# PPU2_And_Connector.net
KiCad netlist of a schematic drawn in Altium Designer
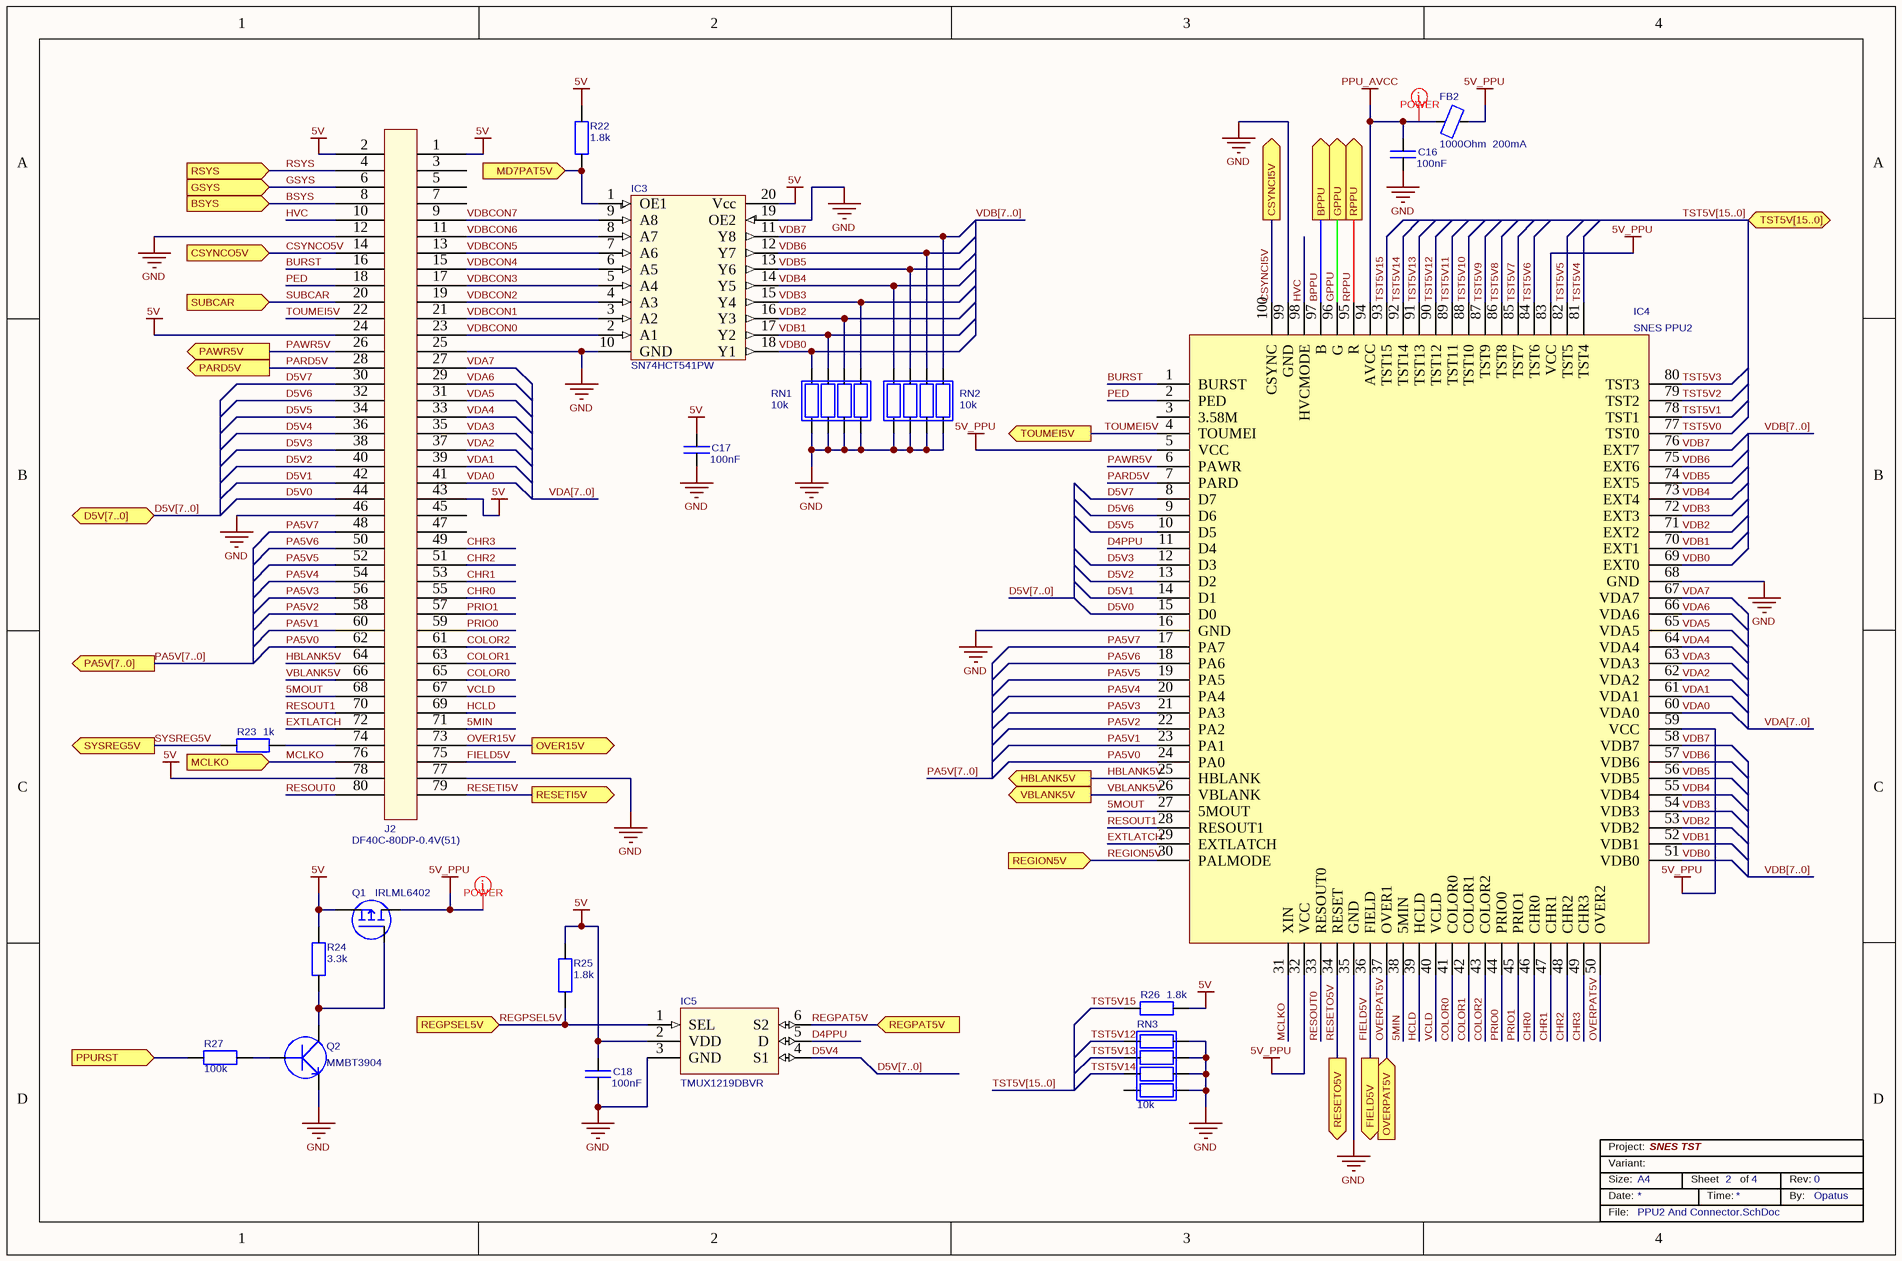
[diagram p0: PPU2 And Connector.SchDoc]

(export (version "E")
  (design (tool "Eeschema 10.0.6"))
  (components
    (comp (ref "C16")
      (value "100nF")
      (footprint "Cap_0402_Chip")
      (fields
        (field (name "TOLERANCE") "±20%")
        (field (name "Comment") "Ceramic Capacitor 100nF 10V ±20% X7R 0402")
      )
      (libsource (lib "PCB") (part "Capacitor"))
    )
    (comp (ref "C17")
      (value "100nF")
      (footprint "Cap_0402_Chip")
      (fields
        (field (name "TOLERANCE") "±20%")
        (field (name "Comment") "Ceramic Capacitor 100nF 10V ±20% X7R 0402")
      )
      (libsource (lib "PCB") (part "Capacitor"))
    )
    (comp (ref "C18")
      (value "100nF")
      (footprint "Cap_0402_Chip")
      (fields
        (field (name "TOLERANCE") "±20%")
        (field (name "Comment") "Ceramic Capacitor 100nF 10V ±20% X7R 0402")
      )
      (libsource (lib "PCB") (part "Capacitor"))
    )
    (comp (ref "FB2")
      (value "1000Ohm  200mA")
      (footprint "Ind_0402_Chip")
      (fields (field (name "MANUFACTURER_PART_NUMBER") "MMZ1005S102CT000"))
      (libsource (lib "PCB") (part "Ferrite Bead"))
    )
    (comp (ref "IC3")
      (value "SN74HCT541")
      (footprint "TSSOP20 Narrow")
      (fields (field (name "MANUFACTURER_PART_NUMBER") "SN74HCT541PW"))
      (libsource (lib "PCB") (part "SN74HCT541"))
    )
    (comp (ref "IC4")
      (value "SNES PPU2")
      (footprint "PPU100Pin")
      (description "PPU2")
      (libsource (lib "PCB") (part "PPU2100Pin"))
    )
    (comp (ref "IC5")
      (value "TMUX1219")
      (footprint "SOT23-6")
      (description "2:1 MUX")
      (fields (field (name "MANUFACTURER_PART_NUMBER") "TMUX1219DBVR"))
      (libsource (lib "PCB") (part "TMUX1219"))
    )
    (comp (ref "J2")
      (value "DF40C-80DP")
      (footprint "DF40C-80DP")
      (description "80Pole Connector")
      (fields (field (name "MANUFACTURER_PART_NUMBER") "DF40C-80DP-0.4V(51)"))
      (libsource (lib "PCB") (part "Conn 80P"))
    )
    (comp (ref "Q1") (value "IRLML6402") (footprint "SOT23_FET") (libsource (lib "PCB") (part "Mosfet1")))
    (comp (ref "Q2") (value "MMBT3904") (footprint "SOT23_Transistor") (libsource (lib "PCB") (part "T_NPN")))
    (comp (ref "R22")
      (value "1.8k")
      (footprint "Res_0402_Chip")
      (fields (field (name "TOLERANCE") "±1%") (field (name "Comment") "Resistor 1.8k 0402 ±1%"))
      (libsource (lib "PCB") (part "R"))
    )
    (comp (ref "R23")
      (value "1k")
      (footprint "Res_0402_Chip")
      (fields (field (name "TOLERANCE") "±1%") (field (name "Comment") "Resistor 1k 0402 ±1%"))
      (libsource (lib "") (part "R_1"))
    )
    (comp (ref "R24")
      (value "3.3k")
      (footprint "Res_0402_Chip")
      (fields (field (name "TOLERANCE") "±1%") (field (name "Comment") "Resistor 3.3k 0402 ±1%"))
      (libsource (lib "PCB") (part "R"))
    )
    (comp (ref "R25")
      (value "1.8k")
      (footprint "Res_0402_Chip")
      (fields (field (name "TOLERANCE") "±1%") (field (name "Comment") "Resistor 1.8k 0402 ±1%"))
      (libsource (lib "PCB") (part "R"))
    )
    (comp (ref "R26")
      (value "1.8k")
      (footprint "Res_0402_Chip")
      (fields (field (name "TOLERANCE") "±1%") (field (name "Comment") "Resistor 1.8k 0402 ±1%"))
      (libsource (lib "") (part "R_2"))
    )
    (comp (ref "R27")
      (value "100k")
      (footprint "Res_0402_Chip")
      (fields (field (name "TOLERANCE") "±1%") (field (name "Comment") "Resistor 100k 0402 ±1%"))
      (libsource (lib "") (part "R_1"))
    )
    (comp (ref "RN1")
      (value "10k")
      (footprint "1206_Array_Chip")
      (fields (field (name "TOLERANCE") "±1%") (field (name "Comment") "Resistor Network 10k 1206 ±1%"))
      (libsource (lib "PCB") (part "RNetwork"))
    )
    (comp (ref "RN2")
      (value "10k")
      (footprint "1206_Array_Chip")
      (fields (field (name "TOLERANCE") "±1%") (field (name "Comment") "Resistor Network 10k 1206 ±1%"))
      (libsource (lib "PCB") (part "RNetwork"))
    )
    (comp (ref "RN3")
      (value "10k")
      (footprint "1206_Array_Chip")
      (fields (field (name "TOLERANCE") "±1%") (field (name "Comment") "Resistor Network 10k 1206 ±1%"))
      (libsource (lib "") (part "RNetwork_1"))
    )
  )
  (nets
    (net (code "1") (name "/5MIN") (class "Default")
      (node (ref "IC4") (pin "38") (pinfunction "5MIN_38") (pintype "passive"))
      (node (ref "J2") (pin "71") (pintype "passive"))
    )
    (net (code "2") (name "/5MOUT") (class "Default")
      (node (ref "IC4") (pin "27") (pinfunction "5MOUT_27") (pintype "passive"))
      (node (ref "J2") (pin "68") (pintype "passive"))
    )
    (net (code "3") (name "/BPPU") (class "Default")
      (node (ref "IC4") (pin "97") (pinfunction "B_97") (pintype "passive"))
    )
    (net (code "4") (name "/BSYS") (class "Default") (node (ref "J2") (pin "8") (pintype "passive")))
    (net (code "5") (name "/BURST") (class "Default")
      (node (ref "IC4") (pin "1") (pinfunction "BURST_1") (pintype "passive"))
      (node (ref "J2") (pin "16") (pintype "passive"))
    )
    (net (code "6") (name "/CHR0") (class "Default")
      (node (ref "IC4") (pin "46") (pinfunction "CHR0_46") (pintype "passive"))
      (node (ref "J2") (pin "55") (pintype "passive"))
    )
    (net (code "7") (name "/CHR1") (class "Default")
      (node (ref "IC4") (pin "47") (pinfunction "CHR1_47") (pintype "passive"))
      (node (ref "J2") (pin "53") (pintype "passive"))
    )
    (net (code "8") (name "/CHR2") (class "Default")
      (node (ref "IC4") (pin "48") (pinfunction "CHR2_48") (pintype "passive"))
      (node (ref "J2") (pin "51") (pintype "passive"))
    )
    (net (code "9") (name "/CHR3") (class "Default")
      (node (ref "IC4") (pin "49") (pinfunction "CHR3_49") (pintype "passive"))
      (node (ref "J2") (pin "49") (pintype "passive"))
    )
    (net (code "10") (name "/COLOR0") (class "Default")
      (node (ref "IC4") (pin "41") (pinfunction "COLOR0_41") (pintype "passive"))
      (node (ref "J2") (pin "65") (pintype "passive"))
    )
    (net (code "11") (name "/COLOR1") (class "Default")
      (node (ref "IC4") (pin "42") (pinfunction "COLOR1_42") (pintype "passive"))
      (node (ref "J2") (pin "63") (pintype "passive"))
    )
    (net (code "12") (name "/COLOR2") (class "Default")
      (node (ref "IC4") (pin "43") (pinfunction "COLOR2_43") (pintype "passive"))
      (node (ref "J2") (pin "61") (pintype "passive"))
    )
    (net (code "13") (name "/CSYNCI5V") (class "Default")
      (node (ref "IC4") (pin "100") (pinfunction "CSYNC_100") (pintype "passive"))
    )
    (net (code "14") (name "/CSYNCO5V") (class "Default") (node (ref "J2") (pin "14") (pintype "passive")))
    (net (code "15") (name "/D4PPU") (class "Default")
      (node (ref "IC4") (pin "11") (pinfunction "D4_11") (pintype "passive"))
      (node (ref "IC5") (pin "5") (pinfunction "D_5") (pintype "bidirectional"))
    )
    (net (code "16") (name "/D5V0") (class "Default")
      (node (ref "IC4") (pin "15") (pinfunction "D0_15") (pintype "passive"))
      (node (ref "J2") (pin "44") (pintype "passive"))
    )
    (net (code "17") (name "/D5V1") (class "Default")
      (node (ref "IC4") (pin "14") (pinfunction "D1_14") (pintype "passive"))
      (node (ref "J2") (pin "42") (pintype "passive"))
    )
    (net (code "18") (name "/D5V2") (class "Default")
      (node (ref "IC4") (pin "13") (pinfunction "D2_13") (pintype "passive"))
      (node (ref "J2") (pin "40") (pintype "passive"))
    )
    (net (code "19") (name "/D5V3") (class "Default")
      (node (ref "IC4") (pin "12") (pinfunction "D3_12") (pintype "passive"))
      (node (ref "J2") (pin "38") (pintype "passive"))
    )
    (net (code "20") (name "/D5V4") (class "Default")
      (node (ref "IC5") (pin "4") (pinfunction "S1_4") (pintype "bidirectional"))
      (node (ref "J2") (pin "36") (pintype "passive"))
    )
    (net (code "21") (name "/D5V5") (class "Default")
      (node (ref "IC4") (pin "10") (pinfunction "D5_10") (pintype "passive"))
      (node (ref "J2") (pin "34") (pintype "passive"))
    )
    (net (code "22") (name "/D5V6") (class "Default")
      (node (ref "IC4") (pin "9") (pinfunction "D6_9") (pintype "passive"))
      (node (ref "J2") (pin "32") (pintype "passive"))
    )
    (net (code "23") (name "/D5V7") (class "Default")
      (node (ref "IC4") (pin "8") (pinfunction "D7_8") (pintype "passive"))
      (node (ref "J2") (pin "30") (pintype "passive"))
    )
    (net (code "25") (name "/EXTLATCH") (class "Default")
      (node (ref "IC4") (pin "29") (pinfunction "EXTLATCH_29") (pintype "passive"))
      (node (ref "J2") (pin "72") (pintype "passive"))
    )
    (net (code "26") (name "/FIELD5V") (class "Default")
      (node (ref "IC4") (pin "36") (pinfunction "FIELD_36") (pintype "passive"))
      (node (ref "J2") (pin "75") (pintype "passive"))
    )
    (net (code "27") (name "/GPPU") (class "Default")
      (node (ref "IC4") (pin "96") (pinfunction "G_96") (pintype "passive"))
    )
    (net (code "28") (name "/GSYS") (class "Default") (node (ref "J2") (pin "6") (pintype "passive")))
    (net (code "29") (name "/HBLANK5V") (class "Default")
      (node (ref "IC4") (pin "25") (pinfunction "HBLANK_25") (pintype "passive"))
      (node (ref "J2") (pin "64") (pintype "passive"))
    )
    (net (code "30") (name "/HCLD") (class "Default")
      (node (ref "IC4") (pin "39") (pinfunction "HCLD_39") (pintype "passive"))
      (node (ref "J2") (pin "69") (pintype "passive"))
    )
    (net (code "31") (name "/HVC") (class "Default")
      (node (ref "IC4") (pin "98") (pinfunction "HVCMODE_98") (pintype "passive"))
      (node (ref "J2") (pin "10") (pintype "passive"))
    )
    (net (code "32") (name "/MCLKO") (class "Default")
      (node (ref "IC4") (pin "31") (pinfunction "XIN_31") (pintype "passive"))
      (node (ref "J2") (pin "76") (pintype "passive"))
    )
    (net (code "33") (name "/MD7PAT5V") (class "Default")
      (node (ref "IC3") (pin "1") (pinfunction "OE1_1") (pintype "input"))
      (node (ref "R22") (pin "2") (pintype "passive"))
    )
    (net (code "34") (name "/OVER15V") (class "Default") (node (ref "J2") (pin "73") (pintype "passive")))
    (net (code "35") (name "/OVERPAT5V") (class "Default")
      (node (ref "IC4") (pin "37") (pinfunction "OVER1_37") (pintype "passive"))
      (node (ref "IC4") (pin "50") (pinfunction "OVER2_50") (pintype "passive"))
    )
    (net (code "36") (name "/PA5V0") (class "Default")
      (node (ref "IC4") (pin "24") (pinfunction "PA0_24") (pintype "passive"))
      (node (ref "J2") (pin "62") (pintype "passive"))
    )
    (net (code "37") (name "/PA5V1") (class "Default")
      (node (ref "IC4") (pin "23") (pinfunction "PA1_23") (pintype "passive"))
      (node (ref "J2") (pin "60") (pintype "passive"))
    )
    (net (code "38") (name "/PA5V2") (class "Default")
      (node (ref "IC4") (pin "22") (pinfunction "PA2_22") (pintype "passive"))
      (node (ref "J2") (pin "58") (pintype "passive"))
    )
    (net (code "39") (name "/PA5V3") (class "Default")
      (node (ref "IC4") (pin "21") (pinfunction "PA3_21") (pintype "passive"))
      (node (ref "J2") (pin "56") (pintype "passive"))
    )
    (net (code "40") (name "/PA5V4") (class "Default")
      (node (ref "IC4") (pin "20") (pinfunction "PA4_20") (pintype "passive"))
      (node (ref "J2") (pin "54") (pintype "passive"))
    )
    (net (code "41") (name "/PA5V5") (class "Default")
      (node (ref "IC4") (pin "19") (pinfunction "PA5_19") (pintype "passive"))
      (node (ref "J2") (pin "52") (pintype "passive"))
    )
    (net (code "42") (name "/PA5V6") (class "Default")
      (node (ref "IC4") (pin "18") (pinfunction "PA6_18") (pintype "passive"))
      (node (ref "J2") (pin "50") (pintype "passive"))
    )
    (net (code "43") (name "/PA5V7") (class "Default")
      (node (ref "IC4") (pin "17") (pinfunction "PA7_17") (pintype "passive"))
      (node (ref "J2") (pin "48") (pintype "passive"))
    )
    (net (code "45") (name "/PARD5V") (class "Default")
      (node (ref "IC4") (pin "7") (pinfunction "PARD_7") (pintype "passive"))
      (node (ref "J2") (pin "28") (pintype "passive"))
    )
    (net (code "46") (name "/PAWR5V") (class "Default")
      (node (ref "IC4") (pin "6") (pinfunction "PAWR_6") (pintype "passive"))
      (node (ref "J2") (pin "26") (pintype "passive"))
    )
    (net (code "47") (name "/PED") (class "Default")
      (node (ref "IC4") (pin "2") (pinfunction "PED_2") (pintype "passive"))
      (node (ref "J2") (pin "18") (pintype "passive"))
    )
    (net (code "48") (name "/PPURST") (class "Default") (node (ref "R27") (pin "1") (pintype "passive")))
    (net (code "49") (name "/PRIO0") (class "Default")
      (node (ref "IC4") (pin "44") (pinfunction "PRIO0_44") (pintype "passive"))
      (node (ref "J2") (pin "59") (pintype "passive"))
    )
    (net (code "50") (name "/PRIO1") (class "Default")
      (node (ref "IC4") (pin "45") (pinfunction "PRIO1_45") (pintype "passive"))
      (node (ref "J2") (pin "57") (pintype "passive"))
    )
    (net (code "51") (name "/REGION5V") (class "Default")
      (node (ref "IC4") (pin "30") (pinfunction "PALMODE_30") (pintype "passive"))
    )
    (net (code "52") (name "/REGPAT5V") (class "Default")
      (node (ref "IC5") (pin "6") (pinfunction "S2_6") (pintype "bidirectional"))
    )
    (net (code "53") (name "/REGPSEL5V") (class "Default")
      (node (ref "IC5") (pin "1") (pinfunction "SEL_1") (pintype "input"))
      (node (ref "R25") (pin "2") (pintype "passive"))
    )
    (net (code "54") (name "/RESETI5V") (class "Default") (node (ref "J2") (pin "79") (pintype "passive")))
    (net (code "55") (name "/RESETO5V") (class "Default")
      (node (ref "IC4") (pin "34") (pinfunction "RESET_34") (pintype "passive"))
    )
    (net (code "56") (name "/RESOUT0") (class "Default")
      (node (ref "IC4") (pin "33") (pinfunction "RESOUT0_33") (pintype "passive"))
      (node (ref "J2") (pin "80") (pintype "passive"))
    )
    (net (code "57") (name "/RESOUT1") (class "Default")
      (node (ref "IC4") (pin "28") (pinfunction "RESOUT1_28") (pintype "passive"))
      (node (ref "J2") (pin "70") (pintype "passive"))
    )
    (net (code "58") (name "/RPPU") (class "Default")
      (node (ref "IC4") (pin "95") (pinfunction "R_95") (pintype "passive"))
    )
    (net (code "59") (name "/RSYS") (class "Default") (node (ref "J2") (pin "4") (pintype "passive")))
    (net (code "60") (name "/SUBCAR") (class "Default") (node (ref "J2") (pin "20") (pintype "passive")))
    (net (code "61") (name "/SYSREG5V") (class "Default") (node (ref "R23") (pin "1") (pintype "passive")))
    (net (code "62") (name "/TOUMEI5V") (class "Default")
      (node (ref "IC4") (pin "4") (pinfunction "TOUMEI_4") (pintype "passive"))
      (node (ref "J2") (pin "22") (pintype "passive"))
    )
    (net (code "63") (name "/TST5V0") (class "Default")
      (node (ref "IC4") (pin "77") (pinfunction "TST0_77") (pintype "passive"))
    )
    (net (code "64") (name "/TST5V1") (class "Default")
      (node (ref "IC4") (pin "78") (pinfunction "TST1_78") (pintype "passive"))
    )
    (net (code "65") (name "/TST5V2") (class "Default")
      (node (ref "IC4") (pin "79") (pinfunction "TST2_79") (pintype "passive"))
    )
    (net (code "66") (name "/TST5V3") (class "Default")
      (node (ref "IC4") (pin "80") (pinfunction "TST3_80") (pintype "passive"))
    )
    (net (code "67") (name "/TST5V4") (class "Default")
      (node (ref "IC4") (pin "81") (pinfunction "TST4_81") (pintype "passive"))
    )
    (net (code "68") (name "/TST5V5") (class "Default")
      (node (ref "IC4") (pin "82") (pinfunction "TST5_82") (pintype "passive"))
    )
    (net (code "69") (name "/TST5V6") (class "Default")
      (node (ref "IC4") (pin "84") (pinfunction "TST6_84") (pintype "passive"))
    )
    (net (code "70") (name "/TST5V7") (class "Default")
      (node (ref "IC4") (pin "85") (pinfunction "TST7_85") (pintype "passive"))
    )
    (net (code "71") (name "/TST5V8") (class "Default")
      (node (ref "IC4") (pin "86") (pinfunction "TST8_86") (pintype "passive"))
    )
    (net (code "72") (name "/TST5V9") (class "Default")
      (node (ref "IC4") (pin "87") (pinfunction "TST9_87") (pintype "passive"))
    )
    (net (code "73") (name "/TST5V10") (class "Default")
      (node (ref "IC4") (pin "88") (pinfunction "TST10_88") (pintype "passive"))
    )
    (net (code "74") (name "/TST5V11") (class "Default")
      (node (ref "IC4") (pin "89") (pinfunction "TST11_89") (pintype "passive"))
    )
    (net (code "75") (name "/TST5V12") (class "Default")
      (node (ref "IC4") (pin "90") (pinfunction "TST12_90") (pintype "passive"))
      (node (ref "RN3") (pin "5") (pintype "passive"))
    )
    (net (code "76") (name "/TST5V13") (class "Default")
      (node (ref "IC4") (pin "91") (pinfunction "TST13_91") (pintype "passive"))
      (node (ref "RN3") (pin "6") (pintype "passive"))
    )
    (net (code "77") (name "/TST5V14") (class "Default")
      (node (ref "IC4") (pin "92") (pinfunction "TST14_92") (pintype "passive"))
      (node (ref "RN3") (pin "7") (pintype "passive"))
    )
    (net (code "78") (name "/TST5V15") (class "Default")
      (node (ref "IC4") (pin "93") (pinfunction "TST15_93") (pintype "passive"))
      (node (ref "R26") (pin "2") (pintype "passive"))
    )
    (net (code "80") (name "/VBLANK5V") (class "Default")
      (node (ref "IC4") (pin "26") (pinfunction "VBLANK_26") (pintype "passive"))
      (node (ref "J2") (pin "66") (pintype "passive"))
    )
    (net (code "81") (name "/VCLD") (class "Default")
      (node (ref "IC4") (pin "40") (pinfunction "VCLD_40") (pintype "passive"))
      (node (ref "J2") (pin "67") (pintype "passive"))
    )
    (net (code "82") (name "/VDA0") (class "Default")
      (node (ref "IC4") (pin "60") (pinfunction "VDA0_60") (pintype "passive"))
      (node (ref "J2") (pin "41") (pintype "passive"))
    )
    (net (code "83") (name "/VDA1") (class "Default")
      (node (ref "IC4") (pin "61") (pinfunction "VDA1_61") (pintype "passive"))
      (node (ref "J2") (pin "39") (pintype "passive"))
    )
    (net (code "84") (name "/VDA2") (class "Default")
      (node (ref "IC4") (pin "62") (pinfunction "VDA2_62") (pintype "passive"))
      (node (ref "J2") (pin "37") (pintype "passive"))
    )
    (net (code "85") (name "/VDA3") (class "Default")
      (node (ref "IC4") (pin "63") (pinfunction "VDA3_63") (pintype "passive"))
      (node (ref "J2") (pin "35") (pintype "passive"))
    )
    (net (code "86") (name "/VDA4") (class "Default")
      (node (ref "IC4") (pin "64") (pinfunction "VDA4_64") (pintype "passive"))
      (node (ref "J2") (pin "33") (pintype "passive"))
    )
    (net (code "87") (name "/VDA5") (class "Default")
      (node (ref "IC4") (pin "65") (pinfunction "VDA5_65") (pintype "passive"))
      (node (ref "J2") (pin "31") (pintype "passive"))
    )
    (net (code "88") (name "/VDA6") (class "Default")
      (node (ref "IC4") (pin "66") (pinfunction "VDA6_66") (pintype "passive"))
      (node (ref "J2") (pin "29") (pintype "passive"))
    )
    (net (code "89") (name "/VDA7") (class "Default")
      (node (ref "IC4") (pin "67") (pinfunction "VDA7_67") (pintype "passive"))
      (node (ref "J2") (pin "27") (pintype "passive"))
    )
    (net (code "91") (name "/VDB0") (class "Default")
      (node (ref "IC3") (pin "18") (pinfunction "Y1_18") (pintype "output"))
      (node (ref "IC4") (pin "51") (pinfunction "VDB0_51") (pintype "passive"))
      (node (ref "IC4") (pin "69") (pinfunction "EXT0_69") (pintype "passive"))
      (node (ref "RN1") (pin "8") (pintype "passive"))
    )
    (net (code "92") (name "/VDB1") (class "Default")
      (node (ref "IC3") (pin "17") (pinfunction "Y2_17") (pintype "output"))
      (node (ref "IC4") (pin "52") (pinfunction "VDB1_52") (pintype "passive"))
      (node (ref "IC4") (pin "70") (pinfunction "EXT1_70") (pintype "passive"))
      (node (ref "RN1") (pin "7") (pintype "passive"))
    )
    (net (code "93") (name "/VDB2") (class "Default")
      (node (ref "IC3") (pin "16") (pinfunction "Y3_16") (pintype "output"))
      (node (ref "IC4") (pin "53") (pinfunction "VDB2_53") (pintype "passive"))
      (node (ref "IC4") (pin "71") (pinfunction "EXT2_71") (pintype "passive"))
      (node (ref "RN1") (pin "6") (pintype "passive"))
    )
    (net (code "94") (name "/VDB3") (class "Default")
      (node (ref "IC3") (pin "15") (pinfunction "Y4_15") (pintype "output"))
      (node (ref "IC4") (pin "54") (pinfunction "VDB3_54") (pintype "passive"))
      (node (ref "IC4") (pin "72") (pinfunction "EXT3_72") (pintype "passive"))
      (node (ref "RN1") (pin "5") (pintype "passive"))
    )
    (net (code "95") (name "/VDB4") (class "Default")
      (node (ref "IC3") (pin "14") (pinfunction "Y5_14") (pintype "output"))
      (node (ref "IC4") (pin "55") (pinfunction "VDB4_55") (pintype "passive"))
      (node (ref "IC4") (pin "73") (pinfunction "EXT4_73") (pintype "passive"))
      (node (ref "RN2") (pin "8") (pintype "passive"))
    )
    (net (code "96") (name "/VDB5") (class "Default")
      (node (ref "IC3") (pin "13") (pinfunction "Y6_13") (pintype "output"))
      (node (ref "IC4") (pin "56") (pinfunction "VDB5_56") (pintype "passive"))
      (node (ref "IC4") (pin "74") (pinfunction "EXT5_74") (pintype "passive"))
      (node (ref "RN2") (pin "7") (pintype "passive"))
    )
    (net (code "97") (name "/VDB6") (class "Default")
      (node (ref "IC3") (pin "12") (pinfunction "Y7_12") (pintype "output"))
      (node (ref "IC4") (pin "57") (pinfunction "VDB6_57") (pintype "passive"))
      (node (ref "IC4") (pin "75") (pinfunction "EXT6_75") (pintype "passive"))
      (node (ref "RN2") (pin "6") (pintype "passive"))
    )
    (net (code "98") (name "/VDB7") (class "Default")
      (node (ref "IC3") (pin "11") (pinfunction "Y8_11") (pintype "output"))
      (node (ref "IC4") (pin "58") (pinfunction "VDB7_58") (pintype "passive"))
      (node (ref "IC4") (pin "76") (pinfunction "EXT7_76") (pintype "passive"))
      (node (ref "RN2") (pin "5") (pintype "passive"))
    )
    (net (code "99") (name "/VDBCON0") (class "Default")
      (node (ref "IC3") (pin "2") (pinfunction "A1_2") (pintype "input"))
      (node (ref "J2") (pin "23") (pintype "passive"))
    )
    (net (code "100") (name "/VDBCON1") (class "Default")
      (node (ref "IC3") (pin "3") (pinfunction "A2_3") (pintype "input"))
      (node (ref "J2") (pin "21") (pintype "passive"))
    )
    (net (code "101") (name "/VDBCON2") (class "Default")
      (node (ref "IC3") (pin "4") (pinfunction "A3_4") (pintype "input"))
      (node (ref "J2") (pin "19") (pintype "passive"))
    )
    (net (code "102") (name "/VDBCON3") (class "Default")
      (node (ref "IC3") (pin "5") (pinfunction "A4_5") (pintype "input"))
      (node (ref "J2") (pin "17") (pintype "passive"))
    )
    (net (code "103") (name "/VDBCON4") (class "Default")
      (node (ref "IC3") (pin "6") (pinfunction "A5_6") (pintype "input"))
      (node (ref "J2") (pin "15") (pintype "passive"))
    )
    (net (code "104") (name "/VDBCON5") (class "Default")
      (node (ref "IC3") (pin "7") (pinfunction "A6_7") (pintype "input"))
      (node (ref "J2") (pin "13") (pintype "passive"))
    )
    (net (code "105") (name "/VDBCON6") (class "Default")
      (node (ref "IC3") (pin "8") (pinfunction "A7_8") (pintype "input"))
      (node (ref "J2") (pin "11") (pintype "passive"))
    )
    (net (code "106") (name "/VDBCON7") (class "Default")
      (node (ref "IC3") (pin "9") (pinfunction "A8_9") (pintype "input"))
      (node (ref "J2") (pin "9") (pintype "passive"))
    )
    (net (code "108") (name "5V") (class "Default")
      (node (ref "C17") (pin "1") (pintype "passive"))
      (node (ref "C18") (pin "1") (pintype "passive"))
      (node (ref "IC3") (pin "20") (pinfunction "Vcc_20") (pintype "power_in"))
      (node (ref "IC5") (pin "2") (pinfunction "VDD_2") (pintype "power_in"))
      (node (ref "J2") (pin "1") (pintype "passive"))
      (node (ref "J2") (pin "2") (pintype "passive"))
      (node (ref "J2") (pin "24") (pintype "passive"))
      (node (ref "J2") (pin "43") (pintype "passive"))
      (node (ref "J2") (pin "78") (pintype "passive"))
      (node (ref "Q1") (pin "S") (pinfunction "S_S") (pintype "passive"))
      (node (ref "R22") (pin "1") (pintype "passive"))
      (node (ref "R24") (pin "1") (pintype "passive"))
      (node (ref "R25") (pin "1") (pintype "passive"))
      (node (ref "R26") (pin "1") (pintype "passive"))
    )
    (net (code "109") (name "5V_PPU") (class "Default")
      (node (ref "FB2") (pin "1") (pintype "passive"))
      (node (ref "IC4") (pin "32") (pinfunction "VCC_32") (pintype "passive"))
      (node (ref "IC4") (pin "5") (pinfunction "VCC_5") (pintype "passive"))
      (node (ref "IC4") (pin "59") (pinfunction "VCC_59") (pintype "passive"))
      (node (ref "IC4") (pin "83") (pinfunction "VCC_83") (pintype "passive"))
      (node (ref "Q1") (pin "D") (pinfunction "D_D") (pintype "passive"))
    )
    (net (code "110") (name "GND") (class "Default")
      (node (ref "C16") (pin "2") (pintype "passive"))
      (node (ref "C17") (pin "2") (pintype "passive"))
      (node (ref "C18") (pin "2") (pintype "passive"))
      (node (ref "IC3") (pin "10") (pinfunction "GND_10") (pintype "power_in"))
      (node (ref "IC3") (pin "19") (pinfunction "OE2_19") (pintype "input"))
      (node (ref "IC4") (pin "16") (pinfunction "GND_16") (pintype "passive"))
      (node (ref "IC4") (pin "35") (pinfunction "GND_35") (pintype "passive"))
      (node (ref "IC4") (pin "68") (pinfunction "GND_68") (pintype "passive"))
      (node (ref "IC4") (pin "99") (pinfunction "GND_99") (pintype "passive"))
      (node (ref "IC5") (pin "3") (pinfunction "GND_3") (pintype "power_in"))
      (node (ref "J2") (pin "12") (pintype "passive"))
      (node (ref "J2") (pin "25") (pintype "passive"))
      (node (ref "J2") (pin "46") (pintype "passive"))
      (node (ref "J2") (pin "77") (pintype "passive"))
      (node (ref "Q2") (pin "E") (pinfunction "E_E") (pintype "passive"))
      (node (ref "RN1") (pin "1") (pintype "passive"))
      (node (ref "RN1") (pin "2") (pintype "passive"))
      (node (ref "RN1") (pin "3") (pintype "passive"))
      (node (ref "RN1") (pin "4") (pintype "passive"))
      (node (ref "RN2") (pin "1") (pintype "passive"))
      (node (ref "RN2") (pin "2") (pintype "passive"))
      (node (ref "RN2") (pin "3") (pintype "passive"))
      (node (ref "RN2") (pin "4") (pintype "passive"))
      (node (ref "RN3") (pin "1") (pintype "passive"))
      (node (ref "RN3") (pin "2") (pintype "passive"))
      (node (ref "RN3") (pin "3") (pintype "passive"))
      (node (ref "RN3") (pin "4") (pintype "passive"))
    )
    (net (code "111") (name "Net-(J2-Pad74)") (class "Default")
      (node (ref "J2") (pin "74") (pintype "passive"))
      (node (ref "R23") (pin "2") (pintype "passive"))
    )
    (net (code "112") (name "Net-(Q1-PadG)") (class "Default")
      (node (ref "Q1") (pin "G") (pinfunction "G_G") (pintype "passive"))
      (node (ref "Q2") (pin "C") (pinfunction "C_C") (pintype "passive"))
      (node (ref "R24") (pin "2") (pintype "passive"))
    )
    (net (code "113") (name "Net-(Q2-PadB)") (class "Default")
      (node (ref "Q2") (pin "B") (pinfunction "B_B") (pintype "passive"))
      (node (ref "R27") (pin "2") (pintype "passive"))
    )
    (net (code "114") (name "PPU_AVCC") (class "Default")
      (node (ref "C16") (pin "1") (pintype "passive"))
      (node (ref "FB2") (pin "2") (pintype "passive"))
      (node (ref "IC4") (pin "94") (pinfunction "AVCC_94") (pintype "passive"))
    )
    (net (code "115") (name "unconnected-(IC4-3.58M-Pad3)") (class "Default")
      (node (ref "IC4") (pin "3") (pinfunction "3.58M_3") (pintype "passive"))
    )
    (net (code "116") (name "unconnected-(J2-Pad3)") (class "Default")
      (node (ref "J2") (pin "3") (pintype "passive"))
    )
    (net (code "117") (name "unconnected-(J2-Pad5)") (class "Default")
      (node (ref "J2") (pin "5") (pintype "passive"))
    )
    (net (code "118") (name "unconnected-(J2-Pad7)") (class "Default")
      (node (ref "J2") (pin "7") (pintype "passive"))
    )
    (net (code "119") (name "unconnected-(J2-Pad45)") (class "Default")
      (node (ref "J2") (pin "45") (pintype "passive"))
    )
    (net (code "120") (name "unconnected-(J2-Pad47)") (class "Default")
      (node (ref "J2") (pin "47") (pintype "passive"))
    )
    (net (code "121") (name "unconnected-(RN3-Pad8)") (class "Default")
      (node (ref "RN3") (pin "8") (pintype "passive"))
    )
  )
)
